# Soprano2G-IMU-173.net
KiCad netlist of a schematic drawn in EAGLE
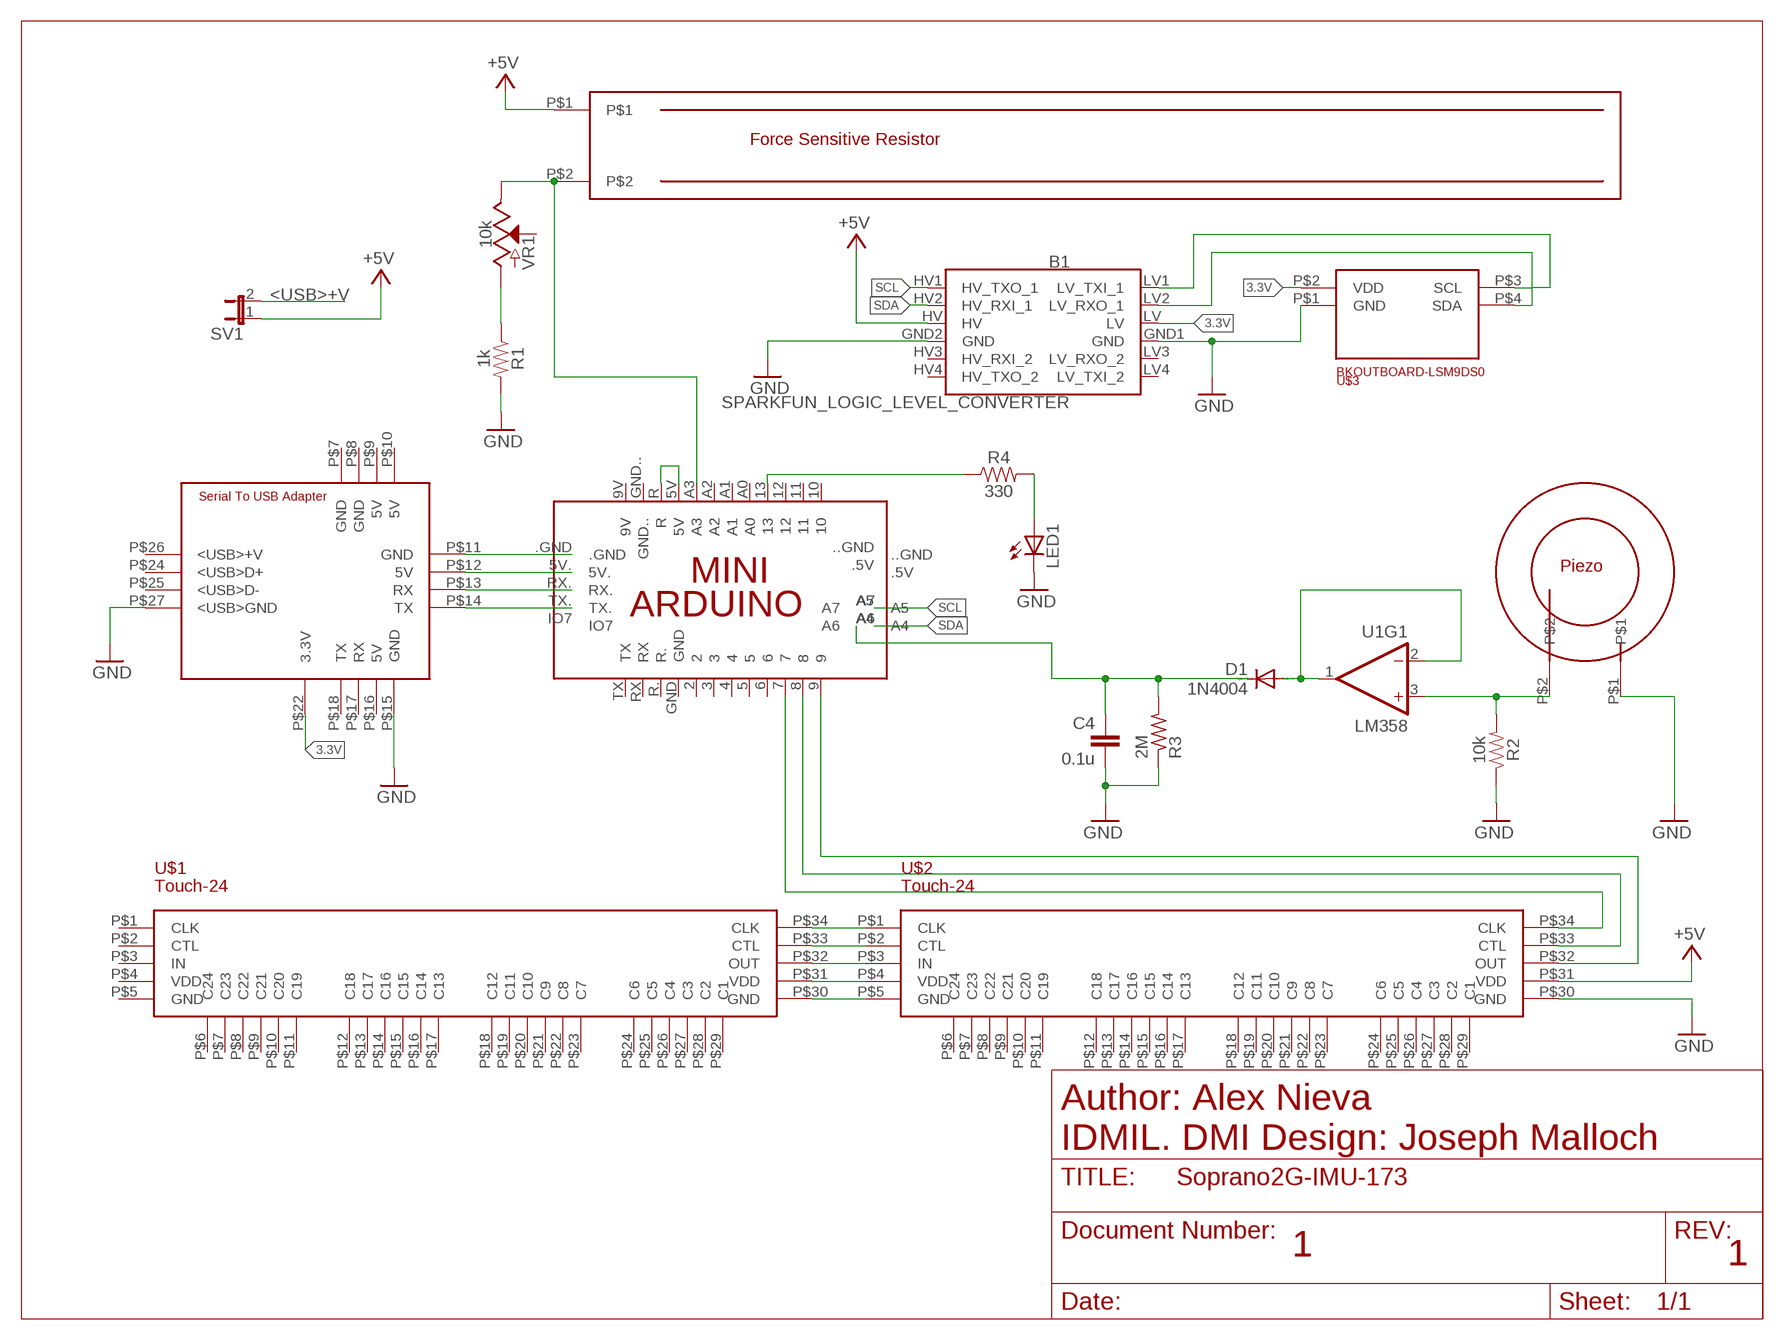
[diagram p0: schematic, sheet 1]

(export (version "E")
  (design (tool "Eeschema 10.0.6"))
  (components
    (comp (ref "B1")
      (value "SPARKFUN_LOGIC_LEVEL_CONVERTER")
      (footprint "eagle-import:SPARKFUN_LOGIC_LEVEL_CONVERTER")
      (libsource (lib "eagle-import") (part "SPARKFUN_LOGIC_LEVEL_CONVERTER"))
    )
    (comp (ref "C4")
      (value "0.1u")
      (footprint "eagle-import:C5B5.5")
      (libsource (lib "eagle-import") (part "C5/5.5"))
    )
    (comp (ref "D1")
      (value "1N4004")
      (footprint "eagle-import:DO41-10")
      (libsource (lib "eagle-import") (part "1N4004"))
    )
    (comp (ref "LED1")
      (value "LED3MM")
      (footprint "eagle-import:LED3MM")
      (libsource (lib "eagle-import") (part "LED3MM"))
    )
    (comp (ref "PCB1")
      (value "ARDUINO_MINI")
      (footprint "eagle-import:ARDUINO_MINI")
      (libsource (lib "eagle-import") (part "ARDUINO_MINI"))
    )
    (comp (ref "R1")
      (value "1k")
      (footprint "eagle-import:AXIAL-0.3")
      (libsource (lib "eagle-import") (part "1KOHM-HORIZ-1/4W-1%"))
    )
    (comp (ref "R2")
      (value "10k")
      (footprint "eagle-import:AXIAL-0.3")
      (libsource (lib "eagle-import") (part "10KOHM-HORIZ-1/4W-1%"))
    )
    (comp (ref "R3")
      (value "2M")
      (footprint "eagle-import:0204_7")
      (libsource (lib "eagle-import") (part "R-US_0204/7"))
    )
    (comp (ref "R4")
      (value "330")
      (footprint "eagle-import:AXIAL-0.3")
      (libsource (lib "eagle-import") (part "1KOHM-HORIZ-1/4W-1%"))
    )
    (comp (ref "SV1")
      (value "JP1E")
      (footprint "eagle-import:JP1")
      (libsource (lib "eagle-import") (part "JP1E"))
    )
    (comp (ref "U$1")
      (value "TOUCH-24TOUCH-24")
      (footprint "eagle-import:TOUCH24")
      (libsource (lib "eagle-import") (part "TOUCH-24TOUCH-24"))
    )
    (comp (ref "U$2")
      (value "TOUCH-24TOUCH-24")
      (footprint "eagle-import:TOUCH24")
      (libsource (lib "eagle-import") (part "TOUCH-24TOUCH-24"))
    )
    (comp (ref "U$3")
      (value "LSM9DS0_IDMIL_BKOUTBOARD")
      (footprint "eagle-import:LSM9DS0_IDMIL_BKOUTBOARD")
      (libsource (lib "eagle-import") (part "LSM9DS0_IDMIL_BKOUTBOARD"))
    )
    (comp (ref "U$4")
      (value "SERIAL_TO_USB_ARDUINO_MINI")
      (footprint "eagle-import:SERIAL_TO_USB_ARDUINO")
      (libsource (lib "eagle-import") (part "SERIAL_TO_USB_ARDUINO_MINI"))
    )
    (comp (ref "U$5")
      (value "FSR_T-STICK")
      (footprint "eagle-import:FSR_T-STICK")
      (libsource (lib "eagle-import") (part "FSR_T-STICK"))
    )
    (comp (ref "U$6")
      (value "PIEZO_TSTICK")
      (footprint "eagle-import:PIEZO_TSTICK")
      (libsource (lib "eagle-import") (part "PIEZO_TSTICK"))
    )
    (comp (ref "U1")
      (value "LM358")
      (footprint "eagle-import:DIP08")
      (libsource (lib "eagle-import") (part "LM358"))
    )
    (comp (ref "VR1")
      (value "10k")
      (footprint "eagle-import:POT-PTH-ALPS")
      (libsource (lib "eagle-import") (part "POTENTIOMETER-PTH-9MM-1/20W-20%"))
    )
  )
  (nets
    (net (code "1") (name "+5V") (class "Default")
      (node (ref "B1") (pin "HV") (pinfunction "HV_HV") (pintype "power_in"))
      (node (ref "PCB1") (pin "5V.") (pinfunction "5V._5V.") (pintype "bidirectional"))
      (node (ref "SV1") (pin "1") (pinfunction "1_1") (pintype "passive"))
      (node (ref "U$2") (pin "P$31") (pinfunction "VDD_P$31") (pintype "bidirectional"))
      (node (ref "U$4") (pin "P$12") (pinfunction "5V_P$12") (pintype "bidirectional"))
      (node (ref "U$5") (pin "P$1") (pinfunction "P$1_P$1") (pintype "bidirectional"))
    )
    (net (code "2") (name "/<USB>+V") (class "Default")
      (node (ref "SV1") (pin "2") (pinfunction "2_2") (pintype "passive"))
    )
    (net (code "3") (name "3.3V") (class "Default")
      (node (ref "B1") (pin "LV") (pinfunction "LV_LV") (pintype "power_in"))
      (node (ref "U$3") (pin "P$2") (pinfunction "VDD_P$2") (pintype "bidirectional"))
      (node (ref "U$4") (pin "P$22") (pinfunction "3.3V_P$22") (pintype "bidirectional"))
    )
    (net (code "4") (name "GND") (class "Default")
      (node (ref "B1") (pin "GND1") (pinfunction "GND_GND1") (pintype "power_in"))
      (node (ref "B1") (pin "GND2") (pinfunction "GND_GND2") (pintype "power_in"))
      (node (ref "C4") (pin "2") (pinfunction "2_2") (pintype "passive"))
      (node (ref "LED1") (pin "K") (pinfunction "C_K") (pintype "passive"))
      (node (ref "R1") (pin "P$2") (pinfunction "2_P$2") (pintype "passive"))
      (node (ref "R2") (pin "P$1") (pinfunction "1_P$1") (pintype "passive"))
      (node (ref "R3") (pin "1") (pinfunction "1_1") (pintype "passive"))
      (node (ref "U$2") (pin "P$30") (pinfunction "GND_P$30") (pintype "bidirectional"))
      (node (ref "U$3") (pin "P$1") (pinfunction "GND_P$1") (pintype "bidirectional"))
      (node (ref "U$4") (pin "P$15") (pinfunction "GND_P$15") (pintype "bidirectional"))
      (node (ref "U$4") (pin "P$27") (pinfunction "<USB>GND_P$27") (pintype "bidirectional"))
      (node (ref "U$6") (pin "P$1") (pinfunction "P$1_P$1") (pintype "bidirectional"))
    )
    (net (code "5") (name "Net-(C4-Pad1)") (class "Default")
      (node (ref "C4") (pin "1") (pinfunction "1_1") (pintype "passive"))
      (node (ref "D1") (pin "C") (pinfunction "C_C") (pintype "passive"))
      (node (ref "PCB1") (pin "A6") (pinfunction "A6_A6") (pintype "bidirectional"))
      (node (ref "R3") (pin "2") (pinfunction "2_2") (pintype "passive"))
    )
    (net (code "6") (name "Net-(PCB1-Pad.GND)") (class "Default")
      (node (ref "PCB1") (pin ".GND") (pinfunction ".GND_.GND") (pintype "bidirectional"))
      (node (ref "U$4") (pin "P$11") (pinfunction "GND_P$11") (pintype "bidirectional"))
    )
    (net (code "7") (name "Net-(PCB1-Pad5V)") (class "Default")
      (node (ref "PCB1") (pin "5V") (pinfunction "5V_5V") (pintype "bidirectional"))
      (node (ref "PCB1") (pin "R") (pinfunction "R_R") (pintype "bidirectional"))
    )
    (net (code "8") (name "Net-(PCB1-Pad7)") (class "Default")
      (node (ref "PCB1") (pin "7") (pinfunction "7_7") (pintype "bidirectional"))
      (node (ref "U$2") (pin "P$34") (pinfunction "CLK_P$34") (pintype "bidirectional"))
    )
    (net (code "9") (name "Net-(PCB1-Pad8)") (class "Default")
      (node (ref "PCB1") (pin "8") (pinfunction "8_8") (pintype "bidirectional"))
      (node (ref "U$2") (pin "P$33") (pinfunction "CTL_P$33") (pintype "bidirectional"))
    )
    (net (code "10") (name "Net-(PCB1-PadRX.)") (class "Default")
      (node (ref "PCB1") (pin "RX.") (pinfunction "RX._RX.") (pintype "bidirectional"))
      (node (ref "U$4") (pin "P$13") (pinfunction "RX_P$13") (pintype "bidirectional"))
    )
    (net (code "11") (name "Net-(PCB1-PadTX.)") (class "Default")
      (node (ref "PCB1") (pin "TX.") (pinfunction "TX._TX.") (pintype "bidirectional"))
      (node (ref "U$4") (pin "P$14") (pinfunction "TX_P$14") (pintype "bidirectional"))
    )
    (net (code "12") (name "Net-(R1-1)") (class "Default")
      (node (ref "R1") (pin "P$1") (pinfunction "1_P$1") (pintype "passive"))
      (node (ref "VR1") (pin "P$3") (pinfunction "A_P$3") (pintype "passive"))
    )
    (net (code "13") (name "Net-(R2-2)") (class "Default")
      (node (ref "R2") (pin "P$2") (pinfunction "2_P$2") (pintype "passive"))
      (node (ref "U$6") (pin "P$2") (pinfunction "P$2_P$2") (pintype "bidirectional"))
      (node (ref "U1") (pin "3") (pinfunction "+IN_3") (pintype "input"))
    )
    (net (code "14") (name "Net-(R4-1)") (class "Default")
      (node (ref "PCB1") (pin "13") (pinfunction "13_13") (pintype "bidirectional"))
      (node (ref "R4") (pin "P$1") (pinfunction "1_P$1") (pintype "passive"))
    )
    (net (code "15") (name "Net-(R4-2)") (class "Default")
      (node (ref "LED1") (pin "A") (pinfunction "A_A") (pintype "passive"))
      (node (ref "R4") (pin "P$2") (pinfunction "2_P$2") (pintype "passive"))
    )
    (net (code "16") (name "Net-(U$1-CLK-PadP$34)") (class "Default")
      (node (ref "U$1") (pin "P$34") (pinfunction "CLK_P$34") (pintype "bidirectional"))
      (node (ref "U$2") (pin "P$1") (pinfunction "CLK_P$1") (pintype "bidirectional"))
    )
    (net (code "17") (name "Net-(U$1-CTL-PadP$33)") (class "Default")
      (node (ref "U$1") (pin "P$33") (pinfunction "CTL_P$33") (pintype "bidirectional"))
      (node (ref "U$2") (pin "P$2") (pinfunction "CTL_P$2") (pintype "bidirectional"))
    )
    (net (code "18") (name "Net-(U$1-GND-PadP$30)") (class "Default")
      (node (ref "U$1") (pin "P$30") (pinfunction "GND_P$30") (pintype "bidirectional"))
      (node (ref "U$2") (pin "P$5") (pinfunction "GND_P$5") (pintype "bidirectional"))
    )
    (net (code "19") (name "Net-(U$1-OUT)") (class "Default")
      (node (ref "U$1") (pin "P$32") (pinfunction "OUT_P$32") (pintype "bidirectional"))
      (node (ref "U$2") (pin "P$3") (pinfunction "IN_P$3") (pintype "bidirectional"))
    )
    (net (code "20") (name "Net-(U$1-VDD-PadP$31)") (class "Default")
      (node (ref "U$1") (pin "P$31") (pinfunction "VDD_P$31") (pintype "bidirectional"))
      (node (ref "U$2") (pin "P$4") (pinfunction "VDD_P$4") (pintype "bidirectional"))
    )
    (net (code "21") (name "Net-(U$2-OUT)") (class "Default")
      (node (ref "PCB1") (pin "9") (pinfunction "9_9") (pintype "bidirectional"))
      (node (ref "U$2") (pin "P$32") (pinfunction "OUT_P$32") (pintype "bidirectional"))
    )
    (net (code "22") (name "Net-(U1A--IN)") (class "Default")
      (node (ref "D1") (pin "A") (pinfunction "A_A") (pintype "passive"))
      (node (ref "U1") (pin "1") (pinfunction "OUT_1") (pintype "output"))
      (node (ref "U1") (pin "2") (pinfunction "-IN_2") (pintype "input"))
    )
    (net (code "23") (name "Net-(VR1-E)") (class "Default")
      (node (ref "PCB1") (pin "A3") (pinfunction "A3_A3") (pintype "bidirectional"))
      (node (ref "U$5") (pin "P$2") (pinfunction "P$2_P$2") (pintype "bidirectional"))
      (node (ref "VR1") (pin "P$1") (pinfunction "E_P$1") (pintype "passive"))
    )
    (net (code "24") (name "SCL") (class "Default")
      (node (ref "B1") (pin "HV1") (pinfunction "HV_TXO_1_HV1") (pintype "bidirectional"))
      (node (ref "B1") (pin "LV1") (pinfunction "LV_TXI_1_LV1") (pintype "bidirectional"))
      (node (ref "PCB1") (pin "A5") (pinfunction "A5_A5") (pintype "bidirectional"))
      (node (ref "U$3") (pin "P$3") (pinfunction "SCL_P$3") (pintype "bidirectional"))
    )
    (net (code "25") (name "SDA") (class "Default")
      (node (ref "B1") (pin "HV2") (pinfunction "HV_RXI_1_HV2") (pintype "bidirectional"))
      (node (ref "B1") (pin "LV2") (pinfunction "LV_RXO_1_LV2") (pintype "bidirectional"))
      (node (ref "PCB1") (pin "A4") (pinfunction "A4_A4") (pintype "bidirectional"))
      (node (ref "U$3") (pin "P$4") (pinfunction "SDA_P$4") (pintype "bidirectional"))
    )
    (net (code "26") (name "unconnected-(B1-HV_RXI_2-PadHV3)") (class "Default")
      (node (ref "B1") (pin "HV3") (pinfunction "HV_RXI_2_HV3") (pintype "bidirectional"))
    )
    (net (code "27") (name "unconnected-(B1-HV_TXO_2-PadHV4)") (class "Default")
      (node (ref "B1") (pin "HV4") (pinfunction "HV_TXO_2_HV4") (pintype "bidirectional"))
    )
    (net (code "28") (name "unconnected-(B1-LV_RXO_2-PadLV3)") (class "Default")
      (node (ref "B1") (pin "LV3") (pinfunction "LV_RXO_2_LV3") (pintype "bidirectional"))
    )
    (net (code "29") (name "unconnected-(B1-LV_TXI_2-PadLV4)") (class "Default")
      (node (ref "B1") (pin "LV4") (pinfunction "LV_TXI_2_LV4") (pintype "bidirectional"))
    )
    (net (code "30") (name "unconnected-(PCB1-Pad..GND)") (class "Default")
      (node (ref "PCB1") (pin "..GND") (pinfunction "..GND_..GND") (pintype "bidirectional"))
    )
    (net (code "31") (name "unconnected-(PCB1-Pad.5V)") (class "Default")
      (node (ref "PCB1") (pin ".5V") (pinfunction ".5V_.5V") (pintype "bidirectional"))
    )
    (net (code "32") (name "unconnected-(PCB1-Pad2)") (class "Default")
      (node (ref "PCB1") (pin "2") (pinfunction "2_2") (pintype "bidirectional"))
    )
    (net (code "33") (name "unconnected-(PCB1-Pad3)") (class "Default")
      (node (ref "PCB1") (pin "3") (pinfunction "3_3") (pintype "bidirectional"))
    )
    (net (code "34") (name "unconnected-(PCB1-Pad4)") (class "Default")
      (node (ref "PCB1") (pin "4") (pinfunction "4_4") (pintype "bidirectional"))
    )
    (net (code "35") (name "unconnected-(PCB1-Pad5)") (class "Default")
      (node (ref "PCB1") (pin "5") (pinfunction "5_5") (pintype "bidirectional"))
    )
    (net (code "36") (name "unconnected-(PCB1-Pad6)") (class "Default")
      (node (ref "PCB1") (pin "6") (pinfunction "6_6") (pintype "bidirectional"))
    )
    (net (code "37") (name "unconnected-(PCB1-Pad9V)") (class "Default")
      (node (ref "PCB1") (pin "9V") (pinfunction "9V_9V") (pintype "bidirectional"))
    )
    (net (code "38") (name "unconnected-(PCB1-Pad10)") (class "Default")
      (node (ref "PCB1") (pin "10") (pinfunction "10_10") (pintype "bidirectional"))
    )
    (net (code "39") (name "unconnected-(PCB1-Pad11)") (class "Default")
      (node (ref "PCB1") (pin "11") (pinfunction "11_11") (pintype "bidirectional"))
    )
    (net (code "40") (name "unconnected-(PCB1-Pad12)") (class "Default")
      (node (ref "PCB1") (pin "12") (pinfunction "12_12") (pintype "bidirectional"))
    )
    (net (code "41") (name "unconnected-(PCB1-PadA0)") (class "Default")
      (node (ref "PCB1") (pin "A0") (pinfunction "A0_A0") (pintype "bidirectional"))
    )
    (net (code "42") (name "unconnected-(PCB1-PadA1)") (class "Default")
      (node (ref "PCB1") (pin "A1") (pinfunction "A1_A1") (pintype "bidirectional"))
    )
    (net (code "43") (name "unconnected-(PCB1-PadA2)") (class "Default")
      (node (ref "PCB1") (pin "A2") (pinfunction "A2_A2") (pintype "bidirectional"))
    )
    (net (code "44") (name "unconnected-(PCB1-PadA7)") (class "Default")
      (node (ref "PCB1") (pin "A7") (pinfunction "A7_A7") (pintype "bidirectional"))
    )
    (net (code "45") (name "unconnected-(PCB1-PadGND)") (class "Default")
      (node (ref "PCB1") (pin "GND") (pinfunction "GND_GND") (pintype "bidirectional"))
    )
    (net (code "46") (name "unconnected-(PCB1-PadGND..)") (class "Default")
      (node (ref "PCB1") (pin "GND..") (pinfunction "GND.._GND..") (pintype "bidirectional"))
    )
    (net (code "47") (name "unconnected-(PCB1-PadIO7)") (class "Default")
      (node (ref "PCB1") (pin "IO7") (pinfunction "IO7_IO7") (pintype "bidirectional"))
    )
    (net (code "48") (name "unconnected-(PCB1-PadR.)") (class "Default")
      (node (ref "PCB1") (pin "R.") (pinfunction "R._R.") (pintype "bidirectional"))
    )
    (net (code "49") (name "unconnected-(PCB1-PadRX)") (class "Default")
      (node (ref "PCB1") (pin "RX") (pinfunction "RX_RX") (pintype "bidirectional"))
    )
    (net (code "50") (name "unconnected-(PCB1-PadTX)") (class "Default")
      (node (ref "PCB1") (pin "TX") (pinfunction "TX_TX") (pintype "bidirectional"))
    )
    (net (code "51") (name "unconnected-(U$1-C1-PadP$29)") (class "Default")
      (node (ref "U$1") (pin "P$29") (pinfunction "C1_P$29") (pintype "bidirectional"))
    )
    (net (code "52") (name "unconnected-(U$1-C2-PadP$28)") (class "Default")
      (node (ref "U$1") (pin "P$28") (pinfunction "C2_P$28") (pintype "bidirectional"))
    )
    (net (code "53") (name "unconnected-(U$1-C3-PadP$27)") (class "Default")
      (node (ref "U$1") (pin "P$27") (pinfunction "C3_P$27") (pintype "bidirectional"))
    )
    (net (code "54") (name "unconnected-(U$1-C4-PadP$26)") (class "Default")
      (node (ref "U$1") (pin "P$26") (pinfunction "C4_P$26") (pintype "bidirectional"))
    )
    (net (code "55") (name "unconnected-(U$1-C5-PadP$25)") (class "Default")
      (node (ref "U$1") (pin "P$25") (pinfunction "C5_P$25") (pintype "bidirectional"))
    )
    (net (code "56") (name "unconnected-(U$1-C6-PadP$24)") (class "Default")
      (node (ref "U$1") (pin "P$24") (pinfunction "C6_P$24") (pintype "bidirectional"))
    )
    (net (code "57") (name "unconnected-(U$1-C7-PadP$23)") (class "Default")
      (node (ref "U$1") (pin "P$23") (pinfunction "C7_P$23") (pintype "bidirectional"))
    )
    (net (code "58") (name "unconnected-(U$1-C8-PadP$22)") (class "Default")
      (node (ref "U$1") (pin "P$22") (pinfunction "C8_P$22") (pintype "bidirectional"))
    )
    (net (code "59") (name "unconnected-(U$1-C9-PadP$21)") (class "Default")
      (node (ref "U$1") (pin "P$21") (pinfunction "C9_P$21") (pintype "bidirectional"))
    )
    (net (code "60") (name "unconnected-(U$1-C10-PadP$20)") (class "Default")
      (node (ref "U$1") (pin "P$20") (pinfunction "C10_P$20") (pintype "bidirectional"))
    )
    (net (code "61") (name "unconnected-(U$1-C11-PadP$19)") (class "Default")
      (node (ref "U$1") (pin "P$19") (pinfunction "C11_P$19") (pintype "bidirectional"))
    )
    (net (code "62") (name "unconnected-(U$1-C12-PadP$18)") (class "Default")
      (node (ref "U$1") (pin "P$18") (pinfunction "C12_P$18") (pintype "bidirectional"))
    )
    (net (code "63") (name "unconnected-(U$1-C13-PadP$17)") (class "Default")
      (node (ref "U$1") (pin "P$17") (pinfunction "C13_P$17") (pintype "bidirectional"))
    )
    (net (code "64") (name "unconnected-(U$1-C14-PadP$16)") (class "Default")
      (node (ref "U$1") (pin "P$16") (pinfunction "C14_P$16") (pintype "bidirectional"))
    )
    (net (code "65") (name "unconnected-(U$1-C15-PadP$15)") (class "Default")
      (node (ref "U$1") (pin "P$15") (pinfunction "C15_P$15") (pintype "bidirectional"))
    )
    (net (code "66") (name "unconnected-(U$1-C16-PadP$14)") (class "Default")
      (node (ref "U$1") (pin "P$14") (pinfunction "C16_P$14") (pintype "bidirectional"))
    )
    (net (code "67") (name "unconnected-(U$1-C17-PadP$13)") (class "Default")
      (node (ref "U$1") (pin "P$13") (pinfunction "C17_P$13") (pintype "bidirectional"))
    )
    (net (code "68") (name "unconnected-(U$1-C18-PadP$12)") (class "Default")
      (node (ref "U$1") (pin "P$12") (pinfunction "C18_P$12") (pintype "bidirectional"))
    )
    (net (code "69") (name "unconnected-(U$1-C19-PadP$11)") (class "Default")
      (node (ref "U$1") (pin "P$11") (pinfunction "C19_P$11") (pintype "bidirectional"))
    )
    (net (code "70") (name "unconnected-(U$1-C20-PadP$10)") (class "Default")
      (node (ref "U$1") (pin "P$10") (pinfunction "C20_P$10") (pintype "bidirectional"))
    )
    (net (code "71") (name "unconnected-(U$1-C21-PadP$9)") (class "Default")
      (node (ref "U$1") (pin "P$9") (pinfunction "C21_P$9") (pintype "bidirectional"))
    )
    (net (code "72") (name "unconnected-(U$1-C22-PadP$8)") (class "Default")
      (node (ref "U$1") (pin "P$8") (pinfunction "C22_P$8") (pintype "bidirectional"))
    )
    (net (code "73") (name "unconnected-(U$1-C23-PadP$7)") (class "Default")
      (node (ref "U$1") (pin "P$7") (pinfunction "C23_P$7") (pintype "bidirectional"))
    )
    (net (code "74") (name "unconnected-(U$1-C24-PadP$6)") (class "Default")
      (node (ref "U$1") (pin "P$6") (pinfunction "C24_P$6") (pintype "bidirectional"))
    )
    (net (code "75") (name "unconnected-(U$1-CLK-PadP$1)") (class "Default")
      (node (ref "U$1") (pin "P$1") (pinfunction "CLK_P$1") (pintype "bidirectional"))
    )
    (net (code "76") (name "unconnected-(U$1-CTL-PadP$2)") (class "Default")
      (node (ref "U$1") (pin "P$2") (pinfunction "CTL_P$2") (pintype "bidirectional"))
    )
    (net (code "77") (name "unconnected-(U$1-GND-PadP$5)") (class "Default")
      (node (ref "U$1") (pin "P$5") (pinfunction "GND_P$5") (pintype "bidirectional"))
    )
    (net (code "78") (name "unconnected-(U$1-IN-PadP$3)") (class "Default")
      (node (ref "U$1") (pin "P$3") (pinfunction "IN_P$3") (pintype "bidirectional"))
    )
    (net (code "79") (name "unconnected-(U$1-VDD-PadP$4)") (class "Default")
      (node (ref "U$1") (pin "P$4") (pinfunction "VDD_P$4") (pintype "bidirectional"))
    )
    (net (code "80") (name "unconnected-(U$2-C1-PadP$29)") (class "Default")
      (node (ref "U$2") (pin "P$29") (pinfunction "C1_P$29") (pintype "bidirectional"))
    )
    (net (code "81") (name "unconnected-(U$2-C2-PadP$28)") (class "Default")
      (node (ref "U$2") (pin "P$28") (pinfunction "C2_P$28") (pintype "bidirectional"))
    )
    (net (code "82") (name "unconnected-(U$2-C3-PadP$27)") (class "Default")
      (node (ref "U$2") (pin "P$27") (pinfunction "C3_P$27") (pintype "bidirectional"))
    )
    (net (code "83") (name "unconnected-(U$2-C4-PadP$26)") (class "Default")
      (node (ref "U$2") (pin "P$26") (pinfunction "C4_P$26") (pintype "bidirectional"))
    )
    (net (code "84") (name "unconnected-(U$2-C5-PadP$25)") (class "Default")
      (node (ref "U$2") (pin "P$25") (pinfunction "C5_P$25") (pintype "bidirectional"))
    )
    (net (code "85") (name "unconnected-(U$2-C6-PadP$24)") (class "Default")
      (node (ref "U$2") (pin "P$24") (pinfunction "C6_P$24") (pintype "bidirectional"))
    )
    (net (code "86") (name "unconnected-(U$2-C7-PadP$23)") (class "Default")
      (node (ref "U$2") (pin "P$23") (pinfunction "C7_P$23") (pintype "bidirectional"))
    )
    (net (code "87") (name "unconnected-(U$2-C8-PadP$22)") (class "Default")
      (node (ref "U$2") (pin "P$22") (pinfunction "C8_P$22") (pintype "bidirectional"))
    )
    (net (code "88") (name "unconnected-(U$2-C9-PadP$21)") (class "Default")
      (node (ref "U$2") (pin "P$21") (pinfunction "C9_P$21") (pintype "bidirectional"))
    )
    (net (code "89") (name "unconnected-(U$2-C10-PadP$20)") (class "Default")
      (node (ref "U$2") (pin "P$20") (pinfunction "C10_P$20") (pintype "bidirectional"))
    )
    (net (code "90") (name "unconnected-(U$2-C11-PadP$19)") (class "Default")
      (node (ref "U$2") (pin "P$19") (pinfunction "C11_P$19") (pintype "bidirectional"))
    )
    (net (code "91") (name "unconnected-(U$2-C12-PadP$18)") (class "Default")
      (node (ref "U$2") (pin "P$18") (pinfunction "C12_P$18") (pintype "bidirectional"))
    )
    (net (code "92") (name "unconnected-(U$2-C13-PadP$17)") (class "Default")
      (node (ref "U$2") (pin "P$17") (pinfunction "C13_P$17") (pintype "bidirectional"))
    )
    (net (code "93") (name "unconnected-(U$2-C14-PadP$16)") (class "Default")
      (node (ref "U$2") (pin "P$16") (pinfunction "C14_P$16") (pintype "bidirectional"))
    )
    (net (code "94") (name "unconnected-(U$2-C15-PadP$15)") (class "Default")
      (node (ref "U$2") (pin "P$15") (pinfunction "C15_P$15") (pintype "bidirectional"))
    )
    (net (code "95") (name "unconnected-(U$2-C16-PadP$14)") (class "Default")
      (node (ref "U$2") (pin "P$14") (pinfunction "C16_P$14") (pintype "bidirectional"))
    )
    (net (code "96") (name "unconnected-(U$2-C17-PadP$13)") (class "Default")
      (node (ref "U$2") (pin "P$13") (pinfunction "C17_P$13") (pintype "bidirectional"))
    )
    (net (code "97") (name "unconnected-(U$2-C18-PadP$12)") (class "Default")
      (node (ref "U$2") (pin "P$12") (pinfunction "C18_P$12") (pintype "bidirectional"))
    )
    (net (code "98") (name "unconnected-(U$2-C19-PadP$11)") (class "Default")
      (node (ref "U$2") (pin "P$11") (pinfunction "C19_P$11") (pintype "bidirectional"))
    )
    (net (code "99") (name "unconnected-(U$2-C20-PadP$10)") (class "Default")
      (node (ref "U$2") (pin "P$10") (pinfunction "C20_P$10") (pintype "bidirectional"))
    )
    (net (code "100") (name "unconnected-(U$2-C21-PadP$9)") (class "Default")
      (node (ref "U$2") (pin "P$9") (pinfunction "C21_P$9") (pintype "bidirectional"))
    )
    (net (code "101") (name "unconnected-(U$2-C22-PadP$8)") (class "Default")
      (node (ref "U$2") (pin "P$8") (pinfunction "C22_P$8") (pintype "bidirectional"))
    )
    (net (code "102") (name "unconnected-(U$2-C23-PadP$7)") (class "Default")
      (node (ref "U$2") (pin "P$7") (pinfunction "C23_P$7") (pintype "bidirectional"))
    )
    (net (code "103") (name "unconnected-(U$2-C24-PadP$6)") (class "Default")
      (node (ref "U$2") (pin "P$6") (pinfunction "C24_P$6") (pintype "bidirectional"))
    )
    (net (code "104") (name "unconnected-(U$4-5V-PadP$9)") (class "Default")
      (node (ref "U$4") (pin "P$9") (pinfunction "5V_P$9") (pintype "bidirectional"))
    )
    (net (code "105") (name "unconnected-(U$4-5V-PadP$10)") (class "Default")
      (node (ref "U$4") (pin "P$10") (pinfunction "5V_P$10") (pintype "bidirectional"))
    )
    (net (code "106") (name "unconnected-(U$4-5V-PadP$16)") (class "Default")
      (node (ref "U$4") (pin "P$16") (pinfunction "5V_P$16") (pintype "bidirectional"))
    )
    (net (code "107") (name "unconnected-(U$4-<USB>+V-PadP$26)") (class "Default")
      (node (ref "U$4") (pin "P$26") (pinfunction "<USB>+V_P$26") (pintype "bidirectional"))
    )
    (net (code "108") (name "unconnected-(U$4-<USB>D+-PadP$24)") (class "Default")
      (node (ref "U$4") (pin "P$24") (pinfunction "<USB>D+_P$24") (pintype "bidirectional"))
    )
    (net (code "109") (name "unconnected-(U$4-<USB>D--PadP$25)") (class "Default")
      (node (ref "U$4") (pin "P$25") (pinfunction "<USB>D-_P$25") (pintype "bidirectional"))
    )
    (net (code "110") (name "unconnected-(U$4-GND-PadP$7)") (class "Default")
      (node (ref "U$4") (pin "P$7") (pinfunction "GND_P$7") (pintype "bidirectional"))
    )
    (net (code "111") (name "unconnected-(U$4-GND-PadP$8)") (class "Default")
      (node (ref "U$4") (pin "P$8") (pinfunction "GND_P$8") (pintype "bidirectional"))
    )
    (net (code "112") (name "unconnected-(U$4-RX-PadP$17)") (class "Default")
      (node (ref "U$4") (pin "P$17") (pinfunction "RX_P$17") (pintype "bidirectional"))
    )
    (net (code "113") (name "unconnected-(U$4-TX-PadP$18)") (class "Default")
      (node (ref "U$4") (pin "P$18") (pinfunction "TX_P$18") (pintype "bidirectional"))
    )
    (net (code "114") (name "unconnected-(VR1-S-PadP$2)") (class "Default")
      (node (ref "VR1") (pin "P$2") (pinfunction "S_P$2") (pintype "passive"))
    )
  )
)
